# Adaptor.net
KiCad netlist of a schematic drawn in EAGLE
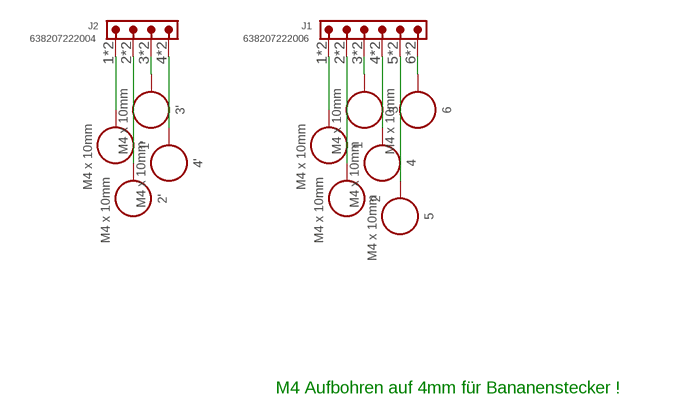
[diagram p0: schematic, sheet 1]

(export (version "E")
  (design (tool "Eeschema 10.0.6"))
  (components
    (comp (ref "1")
      (value "M4 x 10mm")
      (footprint "eagle-import:WA-SMSI_9774100482")
      (libsource (lib "eagle-import") (part "WA-SMSI_9774XXX482_9774100482"))
    )
    (comp (ref "1'")
      (value "M4 x 10mm")
      (footprint "eagle-import:WA-SMSI_9774100482")
      (libsource (lib "eagle-import") (part "WA-SMSI_9774XXX482_9774100482"))
    )
    (comp (ref "2")
      (value "M4 x 10mm")
      (footprint "eagle-import:WA-SMSI_9774100482")
      (libsource (lib "eagle-import") (part "WA-SMSI_9774XXX482_9774100482"))
    )
    (comp (ref "2'")
      (value "M4 x 10mm")
      (footprint "eagle-import:WA-SMSI_9774100482")
      (libsource (lib "eagle-import") (part "WA-SMSI_9774XXX482_9774100482"))
    )
    (comp (ref "3")
      (value "M4 x 10mm")
      (footprint "eagle-import:WA-SMSI_9774100482")
      (libsource (lib "eagle-import") (part "WA-SMSI_9774XXX482_9774100482"))
    )
    (comp (ref "3'")
      (value "M4 x 10mm")
      (footprint "eagle-import:WA-SMSI_9774100482")
      (libsource (lib "eagle-import") (part "WA-SMSI_9774XXX482_9774100482"))
    )
    (comp (ref "4")
      (value "M4 x 10mm")
      (footprint "eagle-import:WA-SMSI_9774100482")
      (libsource (lib "eagle-import") (part "WA-SMSI_9774XXX482_9774100482"))
    )
    (comp (ref "4'")
      (value "M4 x 10mm")
      (footprint "eagle-import:WA-SMSI_9774100482")
      (libsource (lib "eagle-import") (part "WA-SMSI_9774XXX482_9774100482"))
    )
    (comp (ref "5")
      (value "M4 x 10mm")
      (footprint "eagle-import:WA-SMSI_9774100482")
      (libsource (lib "eagle-import") (part "WA-SMSI_9774XXX482_9774100482"))
    )
    (comp (ref "6")
      (value "M4 x 10mm")
      (footprint "eagle-import:WA-SMSI_9774100482")
      (libsource (lib "eagle-import") (part "WA-SMSI_9774XXX482_9774100482"))
    )
    (comp (ref "J1")
      (value "638207222006")
      (footprint "eagle-import:638207222006")
      (libsource (lib "eagle-import") (part "638207222006"))
    )
    (comp (ref "J2")
      (value "638207222004")
      (footprint "eagle-import:638207222004")
      (libsource (lib "eagle-import") (part "638207222004"))
    )
  )
  (nets
    (net (code "1") (name "Net-(1'-Pad1)") (class "Default")
      (node (ref "1'") (pin "1") (pinfunction "1_1") (pintype "passive"))
      (node (ref "J2") (pin "1") (pinfunction "1_1") (pintype "passive"))
      (node (ref "J2") (pin "A1") (pinfunction "1_A1") (pintype "passive"))
    )
    (net (code "2") (name "Net-(1-Pad1)") (class "Default")
      (node (ref "1") (pin "1") (pinfunction "1_1") (pintype "passive"))
      (node (ref "J1") (pin "1") (pinfunction "1_1") (pintype "passive"))
      (node (ref "J1") (pin "A1") (pinfunction "1_A1") (pintype "passive"))
    )
    (net (code "3") (name "Net-(2'-Pad1)") (class "Default")
      (node (ref "2'") (pin "1") (pinfunction "1_1") (pintype "passive"))
      (node (ref "J2") (pin "2") (pinfunction "2_2") (pintype "passive"))
      (node (ref "J2") (pin "A2") (pinfunction "2_A2") (pintype "passive"))
    )
    (net (code "4") (name "Net-(2-Pad1)") (class "Default")
      (node (ref "2") (pin "1") (pinfunction "1_1") (pintype "passive"))
      (node (ref "J1") (pin "2") (pinfunction "2_2") (pintype "passive"))
      (node (ref "J1") (pin "A2") (pinfunction "2_A2") (pintype "passive"))
    )
    (net (code "5") (name "Net-(3'-Pad1)") (class "Default")
      (node (ref "3'") (pin "1") (pinfunction "1_1") (pintype "passive"))
      (node (ref "J2") (pin "3") (pinfunction "3_3") (pintype "passive"))
      (node (ref "J2") (pin "A3") (pinfunction "3_A3") (pintype "passive"))
    )
    (net (code "6") (name "Net-(3-Pad1)") (class "Default")
      (node (ref "3") (pin "1") (pinfunction "1_1") (pintype "passive"))
      (node (ref "J1") (pin "3") (pinfunction "3_3") (pintype "passive"))
      (node (ref "J1") (pin "A3") (pinfunction "3_A3") (pintype "passive"))
    )
    (net (code "7") (name "Net-(4'-Pad1)") (class "Default")
      (node (ref "4'") (pin "1") (pinfunction "1_1") (pintype "passive"))
      (node (ref "J2") (pin "4") (pinfunction "4_4") (pintype "passive"))
      (node (ref "J2") (pin "A4") (pinfunction "4_A4") (pintype "passive"))
    )
    (net (code "8") (name "Net-(4-Pad1)") (class "Default")
      (node (ref "4") (pin "1") (pinfunction "1_1") (pintype "passive"))
      (node (ref "J1") (pin "4") (pinfunction "4_4") (pintype "passive"))
      (node (ref "J1") (pin "A4") (pinfunction "4_A4") (pintype "passive"))
    )
    (net (code "9") (name "Net-(5-Pad1)") (class "Default")
      (node (ref "5") (pin "1") (pinfunction "1_1") (pintype "passive"))
      (node (ref "J1") (pin "5") (pinfunction "5_5") (pintype "passive"))
      (node (ref "J1") (pin "A5") (pinfunction "5_A5") (pintype "passive"))
    )
    (net (code "10") (name "Net-(6-Pad1)") (class "Default")
      (node (ref "6") (pin "1") (pinfunction "1_1") (pintype "passive"))
      (node (ref "J1") (pin "6") (pinfunction "6_6") (pintype "passive"))
      (node (ref "J1") (pin "A6") (pinfunction "6_A6") (pintype "passive"))
    )
  )
)
